# schem.net
KiCad netlist of a schematic drawn in EAGLE
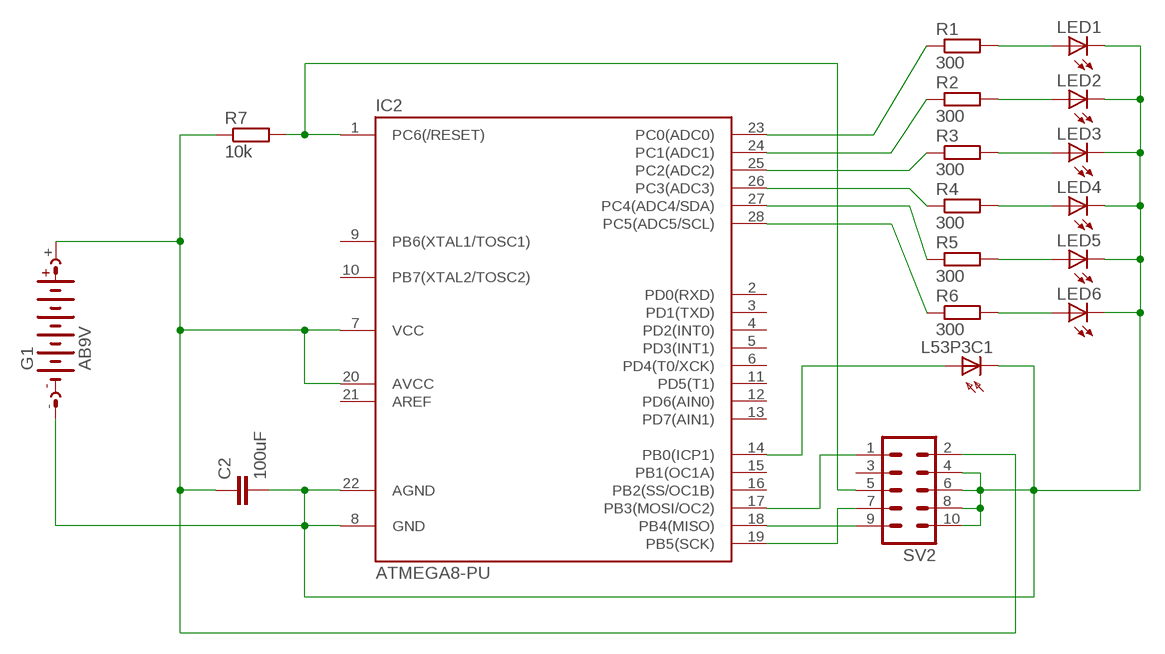
[diagram p0: schematic, sheet 1]

(export (version "E")
  (design (tool "Eeschema 10.0.6"))
  (components
    (comp (ref "C2")
      (value "100uF")
      (footprint "eagle-import:C025-050X050")
      (libsource (lib "eagle-import") (part "C-EU025-050X050"))
    )
    (comp (ref "G1")
      (value "AB9V")
      (footprint "eagle-import:AB9V")
      (libsource (lib "eagle-import") (part "AB9V"))
    )
    (comp (ref "IC2")
      (value "ATMEGA8-PU")
      (footprint "eagle-import:DIL28-3")
      (libsource (lib "eagle-import") (part "ATMEGA8-PU"))
    )
    (comp (ref "L53P3C1")
      (value "BPX65")
      (footprint "eagle-import:BPX65")
      (fields (field (name "MPN") "BPX65."))
      (libsource (lib "eagle-import") (part "BPX65"))
    )
    (comp (ref "LED1")
      (value "LED5MM")
      (footprint "eagle-import:LED5MM")
      (libsource (lib "eagle-import") (part "LED5MM"))
    )
    (comp (ref "LED2")
      (value "LED5MM")
      (footprint "eagle-import:LED5MM")
      (libsource (lib "eagle-import") (part "LED5MM"))
    )
    (comp (ref "LED3")
      (value "LED5MM")
      (footprint "eagle-import:LED5MM")
      (libsource (lib "eagle-import") (part "LED5MM"))
    )
    (comp (ref "LED4")
      (value "LED5MM")
      (footprint "eagle-import:LED5MM")
      (libsource (lib "eagle-import") (part "LED5MM"))
    )
    (comp (ref "LED5")
      (value "LED5MM")
      (footprint "eagle-import:LED5MM")
      (libsource (lib "eagle-import") (part "LED5MM"))
    )
    (comp (ref "LED6")
      (value "LED5MM")
      (footprint "eagle-import:LED5MM")
      (libsource (lib "eagle-import") (part "LED5MM"))
    )
    (comp (ref "R1")
      (value "300")
      (footprint "eagle-import:0204_5")
      (libsource (lib "eagle-import") (part "R-EU_0204/5"))
    )
    (comp (ref "R2")
      (value "300")
      (footprint "eagle-import:0204_5")
      (libsource (lib "eagle-import") (part "R-EU_0204/5"))
    )
    (comp (ref "R3")
      (value "300")
      (footprint "eagle-import:0204_5")
      (libsource (lib "eagle-import") (part "R-EU_0204/5"))
    )
    (comp (ref "R4")
      (value "300")
      (footprint "eagle-import:0204_5")
      (libsource (lib "eagle-import") (part "R-EU_0204/5"))
    )
    (comp (ref "R5")
      (value "300")
      (footprint "eagle-import:0204_5")
      (libsource (lib "eagle-import") (part "R-EU_0204/5"))
    )
    (comp (ref "R6")
      (value "300")
      (footprint "eagle-import:0204_5")
      (libsource (lib "eagle-import") (part "R-EU_0204/5"))
    )
    (comp (ref "R7")
      (value "10k")
      (footprint "eagle-import:0204_5")
      (libsource (lib "eagle-import") (part "R-EU_0204/5"))
    )
    (comp (ref "SV2")
      (value "ML10")
      (footprint "eagle-import:ML10")
      (libsource (lib "eagle-import") (part "ML10"))
    )
  )
  (nets
    (net (code "1") (name "Net-(IC2-AGND)") (class "Default")
      (node (ref "C2") (pin "2") (pinfunction "2_2") (pintype "passive"))
      (node (ref "G1") (pin "-") (pinfunction "-_-") (pintype "passive"))
      (node (ref "IC2") (pin "22") (pinfunction "AGND_22") (pintype "power_in"))
      (node (ref "IC2") (pin "8") (pinfunction "GND_8") (pintype "power_in"))
      (node (ref "L53P3C1") (pin "K") (pinfunction "C_K") (pintype "passive"))
      (node (ref "LED1") (pin "K") (pinfunction "C_K") (pintype "passive"))
      (node (ref "LED2") (pin "K") (pinfunction "C_K") (pintype "passive"))
      (node (ref "LED3") (pin "K") (pinfunction "C_K") (pintype "passive"))
      (node (ref "LED4") (pin "K") (pinfunction "C_K") (pintype "passive"))
      (node (ref "LED5") (pin "K") (pinfunction "C_K") (pintype "passive"))
      (node (ref "LED6") (pin "K") (pinfunction "C_K") (pintype "passive"))
      (node (ref "SV2") (pin "10") (pinfunction "10_10") (pintype "passive"))
      (node (ref "SV2") (pin "4") (pinfunction "4_4") (pintype "passive"))
      (node (ref "SV2") (pin "6") (pinfunction "6_6") (pintype "passive"))
      (node (ref "SV2") (pin "8") (pinfunction "8_8") (pintype "passive"))
    )
    (net (code "2") (name "Net-(IC2-AVCC)") (class "Default")
      (node (ref "C2") (pin "1") (pinfunction "1_1") (pintype "passive"))
      (node (ref "G1") (pin "+") (pinfunction "+_+") (pintype "passive"))
      (node (ref "IC2") (pin "20") (pinfunction "AVCC_20") (pintype "passive"))
      (node (ref "IC2") (pin "7") (pinfunction "VCC_7") (pintype "power_in"))
      (node (ref "R7") (pin "1") (pinfunction "1_1") (pintype "passive"))
      (node (ref "SV2") (pin "2") (pinfunction "2_2") (pintype "passive"))
    )
    (net (code "3") (name "Net-(IC2-PB0(ICP1))") (class "Default")
      (node (ref "IC2") (pin "14") (pinfunction "PB0(ICP1)_14") (pintype "bidirectional"))
      (node (ref "L53P3C1") (pin "A") (pinfunction "A_A") (pintype "passive"))
    )
    (net (code "4") (name "Net-(IC2-PB3(MOSI{slash}OC2))") (class "Default")
      (node (ref "IC2") (pin "17") (pinfunction "PB3(MOSI/OC2)_17") (pintype "bidirectional"))
      (node (ref "SV2") (pin "1") (pinfunction "1_1") (pintype "passive"))
    )
    (net (code "5") (name "Net-(IC2-PB4(MISO))") (class "Default")
      (node (ref "IC2") (pin "18") (pinfunction "PB4(MISO)_18") (pintype "bidirectional"))
      (node (ref "SV2") (pin "9") (pinfunction "9_9") (pintype "passive"))
    )
    (net (code "6") (name "Net-(IC2-PB5(SCK))") (class "Default")
      (node (ref "IC2") (pin "19") (pinfunction "PB5(SCK)_19") (pintype "bidirectional"))
      (node (ref "SV2") (pin "7") (pinfunction "7_7") (pintype "passive"))
    )
    (net (code "7") (name "Net-(IC2-PC0(ADC0))") (class "Default")
      (node (ref "IC2") (pin "23") (pinfunction "PC0(ADC0)_23") (pintype "bidirectional"))
      (node (ref "R1") (pin "1") (pinfunction "1_1") (pintype "passive"))
    )
    (net (code "8") (name "Net-(IC2-PC1(ADC1))") (class "Default")
      (node (ref "IC2") (pin "24") (pinfunction "PC1(ADC1)_24") (pintype "bidirectional"))
      (node (ref "R2") (pin "1") (pinfunction "1_1") (pintype "passive"))
    )
    (net (code "9") (name "Net-(IC2-PC2(ADC2))") (class "Default")
      (node (ref "IC2") (pin "25") (pinfunction "PC2(ADC2)_25") (pintype "bidirectional"))
      (node (ref "R3") (pin "1") (pinfunction "1_1") (pintype "passive"))
    )
    (net (code "10") (name "Net-(IC2-PC3(ADC3))") (class "Default")
      (node (ref "IC2") (pin "26") (pinfunction "PC3(ADC3)_26") (pintype "bidirectional"))
      (node (ref "R4") (pin "1") (pinfunction "1_1") (pintype "passive"))
    )
    (net (code "11") (name "Net-(IC2-PC4(ADC4{slash}SDA))") (class "Default")
      (node (ref "IC2") (pin "27") (pinfunction "PC4(ADC4/SDA)_27") (pintype "bidirectional"))
      (node (ref "R5") (pin "1") (pinfunction "1_1") (pintype "passive"))
    )
    (net (code "12") (name "Net-(IC2-PC5(ADC5{slash}SCL))") (class "Default")
      (node (ref "IC2") (pin "28") (pinfunction "PC5(ADC5/SCL)_28") (pintype "bidirectional"))
      (node (ref "R6") (pin "1") (pinfunction "1_1") (pintype "passive"))
    )
    (net (code "13") (name "Net-(IC2-PC6({slash}RESET))") (class "Default")
      (node (ref "IC2") (pin "1") (pinfunction "PC6(/RESET)_1") (pintype "bidirectional"))
      (node (ref "R7") (pin "2") (pinfunction "2_2") (pintype "passive"))
      (node (ref "SV2") (pin "5") (pinfunction "5_5") (pintype "passive"))
    )
    (net (code "14") (name "Net-(LED1-PadA)") (class "Default")
      (node (ref "LED1") (pin "A") (pinfunction "A_A") (pintype "passive"))
      (node (ref "R1") (pin "2") (pinfunction "2_2") (pintype "passive"))
    )
    (net (code "15") (name "Net-(LED2-PadA)") (class "Default")
      (node (ref "LED2") (pin "A") (pinfunction "A_A") (pintype "passive"))
      (node (ref "R2") (pin "2") (pinfunction "2_2") (pintype "passive"))
    )
    (net (code "16") (name "Net-(LED3-PadA)") (class "Default")
      (node (ref "LED3") (pin "A") (pinfunction "A_A") (pintype "passive"))
      (node (ref "R3") (pin "2") (pinfunction "2_2") (pintype "passive"))
    )
    (net (code "17") (name "Net-(LED4-PadA)") (class "Default")
      (node (ref "LED4") (pin "A") (pinfunction "A_A") (pintype "passive"))
      (node (ref "R4") (pin "2") (pinfunction "2_2") (pintype "passive"))
    )
    (net (code "18") (name "Net-(LED5-PadA)") (class "Default")
      (node (ref "LED5") (pin "A") (pinfunction "A_A") (pintype "passive"))
      (node (ref "R5") (pin "2") (pinfunction "2_2") (pintype "passive"))
    )
    (net (code "19") (name "Net-(LED6-PadA)") (class "Default")
      (node (ref "LED6") (pin "A") (pinfunction "A_A") (pintype "passive"))
      (node (ref "R6") (pin "2") (pinfunction "2_2") (pintype "passive"))
    )
    (net (code "20") (name "unconnected-(IC2-AREF-Pad21)") (class "Default")
      (node (ref "IC2") (pin "21") (pinfunction "AREF_21") (pintype "passive"))
    )
    (net (code "21") (name "unconnected-(IC2-PB1(OC1A)-Pad15)") (class "Default")
      (node (ref "IC2") (pin "15") (pinfunction "PB1(OC1A)_15") (pintype "bidirectional"))
    )
    (net (code "22") (name "unconnected-(IC2-PB2(SS{slash}OC1B)-Pad16)") (class "Default")
      (node (ref "IC2") (pin "16") (pinfunction "PB2(SS/OC1B)_16") (pintype "bidirectional"))
    )
    (net (code "23") (name "unconnected-(IC2-PB6(XTAL1{slash}TOSC1)-Pad9)") (class "Default")
      (node (ref "IC2") (pin "9") (pinfunction "PB6(XTAL1/TOSC1)_9") (pintype "bidirectional"))
    )
    (net (code "24") (name "unconnected-(IC2-PB7(XTAL2{slash}TOSC2)-Pad10)") (class "Default")
      (node (ref "IC2") (pin "10") (pinfunction "PB7(XTAL2/TOSC2)_10") (pintype "bidirectional"))
    )
    (net (code "25") (name "unconnected-(IC2-PD0(RXD)-Pad2)") (class "Default")
      (node (ref "IC2") (pin "2") (pinfunction "PD0(RXD)_2") (pintype "bidirectional"))
    )
    (net (code "26") (name "unconnected-(IC2-PD1(TXD)-Pad3)") (class "Default")
      (node (ref "IC2") (pin "3") (pinfunction "PD1(TXD)_3") (pintype "bidirectional"))
    )
    (net (code "27") (name "unconnected-(IC2-PD2(INT0)-Pad4)") (class "Default")
      (node (ref "IC2") (pin "4") (pinfunction "PD2(INT0)_4") (pintype "bidirectional"))
    )
    (net (code "28") (name "unconnected-(IC2-PD3(INT1)-Pad5)") (class "Default")
      (node (ref "IC2") (pin "5") (pinfunction "PD3(INT1)_5") (pintype "bidirectional"))
    )
    (net (code "29") (name "unconnected-(IC2-PD4(T0{slash}XCK)-Pad6)") (class "Default")
      (node (ref "IC2") (pin "6") (pinfunction "PD4(T0/XCK)_6") (pintype "bidirectional"))
    )
    (net (code "30") (name "unconnected-(IC2-PD5(T1)-Pad11)") (class "Default")
      (node (ref "IC2") (pin "11") (pinfunction "PD5(T1)_11") (pintype "bidirectional"))
    )
    (net (code "31") (name "unconnected-(IC2-PD6(AIN0)-Pad12)") (class "Default")
      (node (ref "IC2") (pin "12") (pinfunction "PD6(AIN0)_12") (pintype "bidirectional"))
    )
    (net (code "32") (name "unconnected-(IC2-PD7(AIN1)-Pad13)") (class "Default")
      (node (ref "IC2") (pin "13") (pinfunction "PD7(AIN1)_13") (pintype "bidirectional"))
    )
    (net (code "33") (name "unconnected-(SV2-Pad3)") (class "Default")
      (node (ref "SV2") (pin "3") (pinfunction "3_3") (pintype "passive"))
    )
  )
)
